# schematic.net
KiCad netlist of a schematic drawn in EAGLE
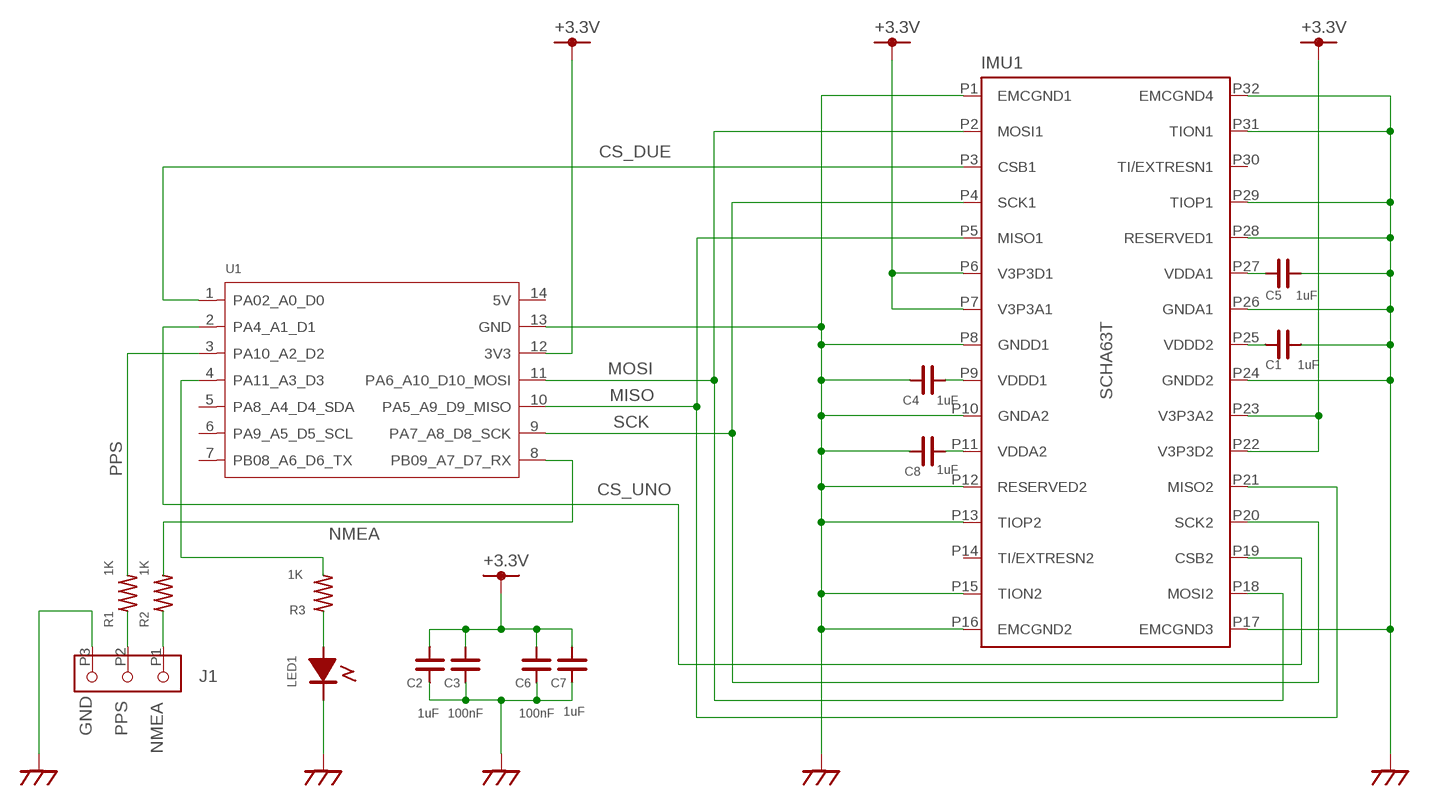
[diagram p0: schematic, sheet 1]

(export (version "E")
  (design (tool "Eeschema 10.0.6"))
  (components
    (comp (ref "C1")
      (value "1uF")
      (footprint "eagle-import:C1608")
      (libsource (lib "eagle-import") (part "C1608"))
    )
    (comp (ref "C2")
      (value "1uF")
      (footprint "eagle-import:C1608")
      (libsource (lib "eagle-import") (part "C1608"))
    )
    (comp (ref "C3")
      (value "100nF")
      (footprint "eagle-import:C1608")
      (libsource (lib "eagle-import") (part "C1608"))
    )
    (comp (ref "C4")
      (value "1uF")
      (footprint "eagle-import:C1608")
      (libsource (lib "eagle-import") (part "C1608"))
    )
    (comp (ref "C5")
      (value "1uF")
      (footprint "eagle-import:C1608")
      (libsource (lib "eagle-import") (part "C1608"))
    )
    (comp (ref "C6")
      (value "100nF")
      (footprint "eagle-import:C1608")
      (libsource (lib "eagle-import") (part "C1608"))
    )
    (comp (ref "C7")
      (value "1uF")
      (footprint "eagle-import:C1608")
      (libsource (lib "eagle-import") (part "C1608"))
    )
    (comp (ref "C8")
      (value "1uF")
      (footprint "eagle-import:C1608")
      (libsource (lib "eagle-import") (part "C1608"))
    )
    (comp (ref "IMU1")
      (value "SCHA63T")
      (footprint "eagle-import:SOIC-32")
      (libsource (lib "eagle-import") (part "SCHA63T"))
    )
    (comp (ref "J1")
      (value "JST_SH_10_3P")
      (footprint "eagle-import:JST_SH_10_3P")
      (libsource (lib "eagle-import") (part "JST_SH_10_3P"))
    )
    (comp (ref "LED1")
      (value "LED1608")
      (footprint "eagle-import:LED_1608")
      (libsource (lib "eagle-import") (part "LED1608"))
    )
    (comp (ref "R1")
      (value "1K")
      (footprint "eagle-import:C1608")
      (libsource (lib "eagle-import") (part "R1608"))
    )
    (comp (ref "R2")
      (value "1K")
      (footprint "eagle-import:C1608")
      (libsource (lib "eagle-import") (part "R1608"))
    )
    (comp (ref "R3")
      (value "1K")
      (footprint "eagle-import:C1608")
      (libsource (lib "eagle-import") (part "R1608"))
    )
    (comp (ref "U1")
      (value "MOUDLE-SEEEDUINO-XIAO")
      (footprint "eagle-import:MOUDLE14P-2.54-21X17.8MM")
      (libsource (lib "eagle-import") (part "MOUDLE-SEEEDUINO-XIAO"))
    )
  )
  (nets
    (net (code "1") (name "+3.3V") (class "Default")
      (node (ref "C2") (pin "2") (pinfunction "2_2") (pintype "passive"))
      (node (ref "C3") (pin "2") (pinfunction "2_2") (pintype "passive"))
      (node (ref "C6") (pin "2") (pinfunction "2_2") (pintype "passive"))
      (node (ref "C7") (pin "2") (pinfunction "2_2") (pintype "passive"))
      (node (ref "IMU1") (pin "P22") (pinfunction "V3P3D2_P22") (pintype "power_in"))
      (node (ref "IMU1") (pin "P23") (pinfunction "V3P3A2_P23") (pintype "power_in"))
      (node (ref "IMU1") (pin "P6") (pinfunction "V3P3D1_P6") (pintype "power_in"))
      (node (ref "IMU1") (pin "P7") (pinfunction "V3P3A1_P7") (pintype "power_in"))
      (node (ref "U1") (pin "12") (pinfunction "3V3_12") (pintype "bidirectional"))
    )
    (net (code "2") (name "/CS_DUE") (class "Default")
      (node (ref "IMU1") (pin "P3") (pinfunction "CSB1_P3") (pintype "bidirectional"))
      (node (ref "U1") (pin "1") (pinfunction "PA02_A0_D0_1") (pintype "bidirectional"))
    )
    (net (code "3") (name "/CS_UNO") (class "Default")
      (node (ref "IMU1") (pin "P19") (pinfunction "CSB2_P19") (pintype "bidirectional"))
      (node (ref "U1") (pin "2") (pinfunction "PA4_A1_D1_2") (pintype "bidirectional"))
    )
    (net (code "4") (name "/MISO") (class "Default")
      (node (ref "IMU1") (pin "P21") (pinfunction "MISO2_P21") (pintype "bidirectional"))
      (node (ref "IMU1") (pin "P5") (pinfunction "MISO1_P5") (pintype "bidirectional"))
      (node (ref "U1") (pin "10") (pinfunction "PA5_A9_D9_MISO_10") (pintype "bidirectional"))
    )
    (net (code "5") (name "/MOSI") (class "Default")
      (node (ref "IMU1") (pin "P18") (pinfunction "MOSI2_P18") (pintype "bidirectional"))
      (node (ref "IMU1") (pin "P2") (pinfunction "MOSI1_P2") (pintype "bidirectional"))
      (node (ref "U1") (pin "11") (pinfunction "PA6_A10_D10_MOSI_11") (pintype "bidirectional"))
    )
    (net (code "6") (name "/NMEA") (class "Default")
      (node (ref "R2") (pin "2") (pinfunction "P$2_2") (pintype "passive"))
      (node (ref "U1") (pin "8") (pinfunction "PB09_A7_D7_RX_8") (pintype "bidirectional"))
    )
    (net (code "7") (name "/PPS") (class "Default")
      (node (ref "R1") (pin "2") (pinfunction "P$2_2") (pintype "passive"))
      (node (ref "U1") (pin "3") (pinfunction "PA10_A2_D2_3") (pintype "bidirectional"))
    )
    (net (code "8") (name "/SCK") (class "Default")
      (node (ref "IMU1") (pin "P20") (pinfunction "SCK2_P20") (pintype "bidirectional"))
      (node (ref "IMU1") (pin "P4") (pinfunction "SCK1_P4") (pintype "bidirectional"))
      (node (ref "U1") (pin "9") (pinfunction "PA7_A8_D8_SCK_9") (pintype "bidirectional"))
    )
    (net (code "9") (name "GND") (class "Default")
      (node (ref "C1") (pin "2") (pinfunction "2_2") (pintype "passive"))
      (node (ref "C2") (pin "1") (pinfunction "1_1") (pintype "passive"))
      (node (ref "C3") (pin "1") (pinfunction "1_1") (pintype "passive"))
      (node (ref "C4") (pin "1") (pinfunction "1_1") (pintype "passive"))
      (node (ref "C5") (pin "2") (pinfunction "2_2") (pintype "passive"))
      (node (ref "C6") (pin "1") (pinfunction "1_1") (pintype "passive"))
      (node (ref "C7") (pin "1") (pinfunction "1_1") (pintype "passive"))
      (node (ref "C8") (pin "1") (pinfunction "1_1") (pintype "passive"))
      (node (ref "IMU1") (pin "P1") (pinfunction "EMCGND1_P1") (pintype "power_in"))
      (node (ref "IMU1") (pin "P10") (pinfunction "GNDA2_P10") (pintype "power_in"))
      (node (ref "IMU1") (pin "P12") (pinfunction "RESERVED2_P12") (pintype "bidirectional"))
      (node (ref "IMU1") (pin "P13") (pinfunction "TIOP2_P13") (pintype "bidirectional"))
      (node (ref "IMU1") (pin "P15") (pinfunction "TION2_P15") (pintype "bidirectional"))
      (node (ref "IMU1") (pin "P16") (pinfunction "EMCGND2_P16") (pintype "power_in"))
      (node (ref "IMU1") (pin "P17") (pinfunction "EMCGND3_P17") (pintype "power_in"))
      (node (ref "IMU1") (pin "P24") (pinfunction "GNDD2_P24") (pintype "power_in"))
      (node (ref "IMU1") (pin "P26") (pinfunction "GNDA1_P26") (pintype "power_in"))
      (node (ref "IMU1") (pin "P28") (pinfunction "RESERVED1_P28") (pintype "bidirectional"))
      (node (ref "IMU1") (pin "P29") (pinfunction "TIOP1_P29") (pintype "bidirectional"))
      (node (ref "IMU1") (pin "P31") (pinfunction "TION1_P31") (pintype "bidirectional"))
      (node (ref "IMU1") (pin "P32") (pinfunction "EMCGND4_P32") (pintype "power_in"))
      (node (ref "IMU1") (pin "P8") (pinfunction "GNDD1_P8") (pintype "power_in"))
      (node (ref "J1") (pin "P3") (pinfunction "P3_P3") (pintype "bidirectional"))
      (node (ref "LED1") (pin "2") (pinfunction "P$2_2") (pintype "passive"))
      (node (ref "U1") (pin "13") (pinfunction "GND_13") (pintype "bidirectional"))
    )
    (net (code "10") (name "Net-(IMU1-VDDA1)") (class "Default")
      (node (ref "C5") (pin "1") (pinfunction "1_1") (pintype "passive"))
      (node (ref "IMU1") (pin "P27") (pinfunction "VDDA1_P27") (pintype "power_in"))
    )
    (net (code "11") (name "Net-(IMU1-VDDA2)") (class "Default")
      (node (ref "C8") (pin "2") (pinfunction "2_2") (pintype "passive"))
      (node (ref "IMU1") (pin "P11") (pinfunction "VDDA2_P11") (pintype "power_in"))
    )
    (net (code "12") (name "Net-(IMU1-VDDD1)") (class "Default")
      (node (ref "C4") (pin "2") (pinfunction "2_2") (pintype "passive"))
      (node (ref "IMU1") (pin "P9") (pinfunction "VDDD1_P9") (pintype "power_in"))
    )
    (net (code "13") (name "Net-(IMU1-VDDD2)") (class "Default")
      (node (ref "C1") (pin "1") (pinfunction "1_1") (pintype "passive"))
      (node (ref "IMU1") (pin "P25") (pinfunction "VDDD2_P25") (pintype "power_in"))
    )
    (net (code "14") (name "Net-(LED1-+)") (class "Default")
      (node (ref "LED1") (pin "1") (pinfunction "+_1") (pintype "passive"))
      (node (ref "R3") (pin "1") (pinfunction "P$1_1") (pintype "passive"))
    )
    (net (code "15") (name "Net-(R1-P$1)") (class "Default")
      (node (ref "J1") (pin "P2") (pinfunction "P2_P2") (pintype "bidirectional"))
      (node (ref "R1") (pin "1") (pinfunction "P$1_1") (pintype "passive"))
    )
    (net (code "16") (name "Net-(R2-P$1)") (class "Default")
      (node (ref "J1") (pin "P1") (pinfunction "P1_P1") (pintype "bidirectional"))
      (node (ref "R2") (pin "1") (pinfunction "P$1_1") (pintype "passive"))
    )
    (net (code "17") (name "Net-(R3-P$2)") (class "Default")
      (node (ref "R3") (pin "2") (pinfunction "P$2_2") (pintype "passive"))
      (node (ref "U1") (pin "4") (pinfunction "PA11_A3_D3_4") (pintype "bidirectional"))
    )
    (net (code "18") (name "unconnected-(IMU1-TI{slash}EXTRESN1-PadP30)") (class "Default")
      (node (ref "IMU1") (pin "P30") (pinfunction "TI/EXTRESN1_P30") (pintype "bidirectional"))
    )
    (net (code "19") (name "unconnected-(IMU1-TI{slash}EXTRESN2-PadP14)") (class "Default")
      (node (ref "IMU1") (pin "P14") (pinfunction "TI/EXTRESN2_P14") (pintype "bidirectional"))
    )
    (net (code "20") (name "unconnected-(U1-5V-Pad14)") (class "Default")
      (node (ref "U1") (pin "14") (pinfunction "5V_14") (pintype "bidirectional"))
    )
    (net (code "21") (name "unconnected-(U1-PA8_A4_D4_SDA-Pad5)") (class "Default")
      (node (ref "U1") (pin "5") (pinfunction "PA8_A4_D4_SDA_5") (pintype "bidirectional"))
    )
    (net (code "22") (name "unconnected-(U1-PA9_A5_D5_SCL-Pad6)") (class "Default")
      (node (ref "U1") (pin "6") (pinfunction "PA9_A5_D5_SCL_6") (pintype "bidirectional"))
    )
    (net (code "23") (name "unconnected-(U1-PB08_A6_D6_TX-Pad7)") (class "Default")
      (node (ref "U1") (pin "7") (pinfunction "PB08_A6_D6_TX_7") (pintype "bidirectional"))
    )
  )
)
